# BMS_rev2.net
KiCad netlist of a schematic drawn in Altium Designer
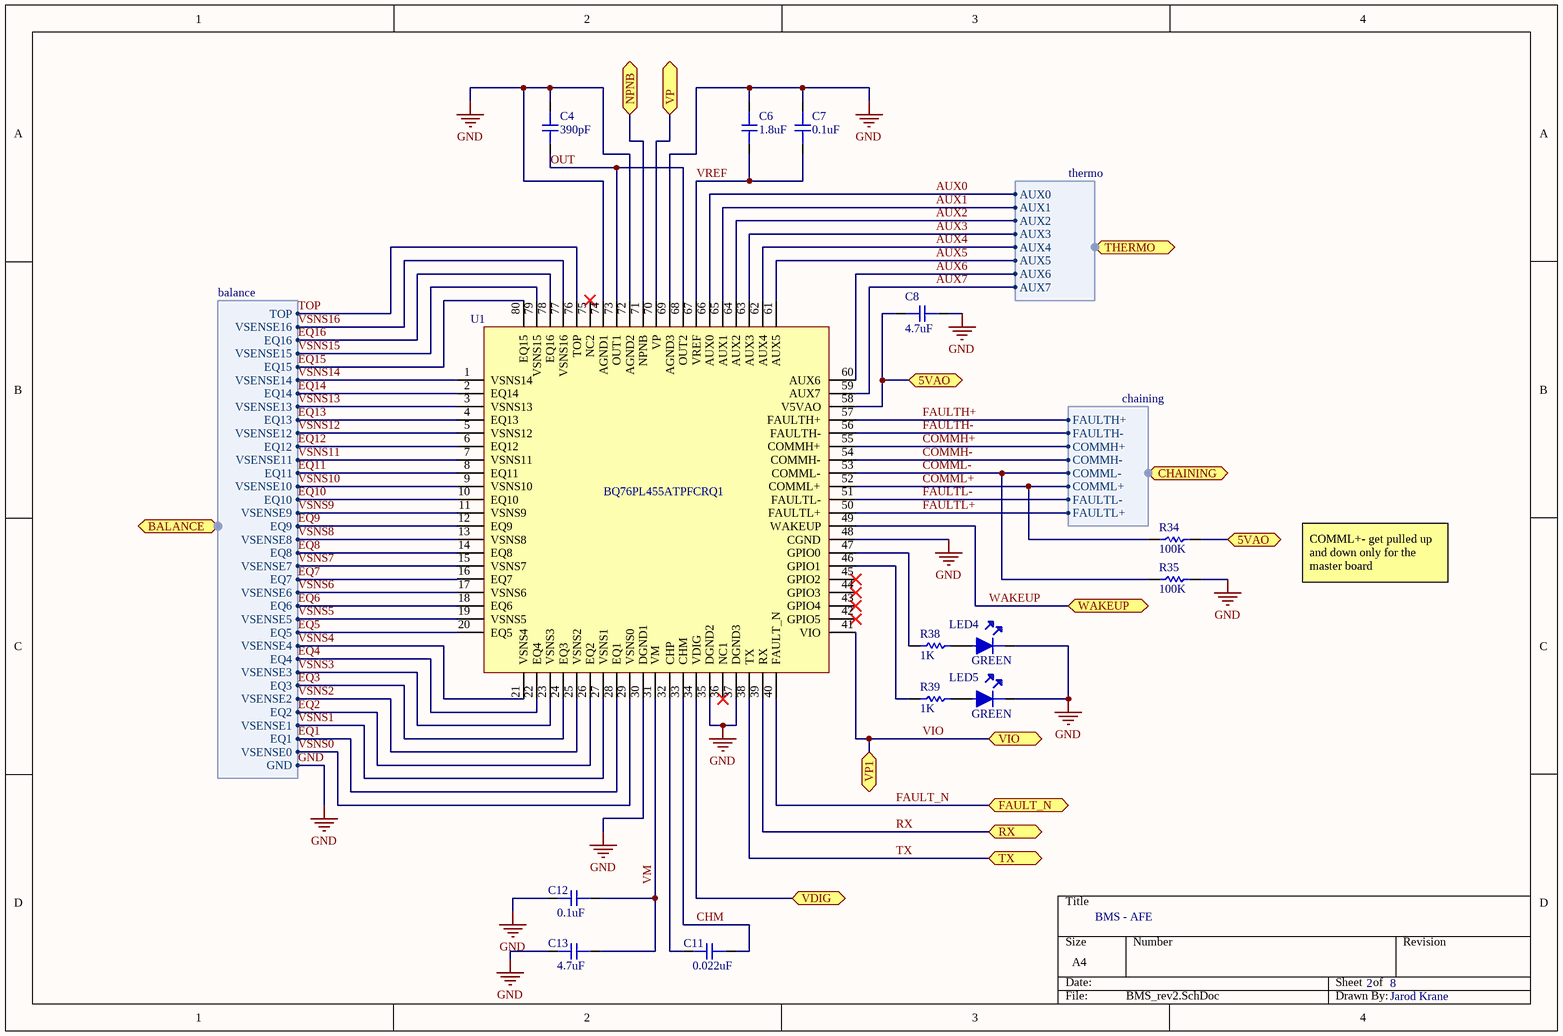
[diagram p0: BMS_rev2.SchDoc]

(export (version "E")
  (design (tool "Eeschema 10.0.6"))
  (components
    (comp (ref "C4")
      (value "390pF")
      (footprint "0805 CAP")
      (description "CAP CER 390PF 50V C0G/NP0 0805")
      (fields
        (field (name "MANUFACTURER") "Kyocera AVX")
        (field (name "MANUFACTURER PART NUMBER") "08055A391JAT2A")
      )
      (libsource (lib "parts") (part "08055A391JAT2A"))
    )
    (comp (ref "C6")
      (value "1.8uF")
      (footprint "1210 cap")
      (description "CAP CER 1.8UF 25V X7R 1210")
      (fields
        (field (name "MANUFACTURER") "KEMET")
        (field (name "MANUFACTURER PART NUMBER") "C1210C185K3RACTU")
      )
      (libsource (lib "parts") (part "C1210C185K3RACTU"))
    )
    (comp (ref "C7")
      (value "0.1uF")
      (footprint "0603 CAP - duplicate")
      (description "CAP CER 0.1UF 50V X7R 0603")
      (fields
        (field (name "MANUFACTURER") "Kyocera AVX")
        (field (name "MANUFACTURER PART NUMBER") "06035C104KAZ2A")
      )
      (libsource (lib "parts") (part "06035C104KAZ2A"))
    )
    (comp (ref "C8")
      (value "4.7uF")
      (footprint "0805 CAP")
      (description "CAP CER 4.7UF 16V X7R 0805")
      (fields
        (field (name "MANUFACTURER") "Samsung")
        (field (name "MANUFACTURER PART NUMBER") "CL21B475KOFNFNE")
      )
      (libsource (lib "parts") (part "CL21B475KOFNFNE"))
    )
    (comp (ref "C11")
      (value "0.022uF")
      (footprint "0603 CAP - duplicate")
      (description "CAP CER 0.022UF 50V X7R 0603")
      (fields
        (field (name "MANUFACTURER") "TDK")
        (field (name "MANUFACTURER PART NUMBER") "C1608X7R1H223K080AA")
      )
      (libsource (lib "parts") (part "C1608X7R1H223K080AA"))
    )
    (comp (ref "C12")
      (value "0.1uF")
      (footprint "0603 CAP - duplicate")
      (description "CAP CER 0.1UF 50V X7R 0603")
      (fields
        (field (name "MANUFACTURER") "Kyocera AVX")
        (field (name "MANUFACTURER PART NUMBER") "06035C104KAZ2A")
      )
      (libsource (lib "parts") (part "06035C104KAZ2A"))
    )
    (comp (ref "C13")
      (value "4.7uF")
      (footprint "0805 CAP")
      (description "CAP CER 4.7UF 16V X7R 0805")
      (fields
        (field (name "MANUFACTURER") "Samsung")
        (field (name "MANUFACTURER PART NUMBER") "CL21B475KOFNFNE")
      )
      (libsource (lib "parts") (part "CL21B475KOFNFNE"))
    )
    (comp (ref "LED4")
      (value "GREEN")
      (footprint "LED2")
      (description "LED GREEN CLEAR 0603 SMD")
      (fields
        (field (name "MANUFACTURER") "Wurth Electronics")
        (field (name "MANUFACTURER PART NUMBER") "150060VS75000")
      )
      (libsource (lib "parts") (part "150060VS75000"))
    )
    (comp (ref "LED5")
      (value "GREEN")
      (footprint "LED2")
      (description "LED GREEN CLEAR 0603 SMD")
      (fields
        (field (name "MANUFACTURER") "Wurth Electronics")
        (field (name "MANUFACTURER PART NUMBER") "150060VS75000")
      )
      (libsource (lib "parts") (part "150060VS75000"))
    )
    (comp (ref "R34")
      (value "100K")
      (footprint "0603 RES")
      (description "RES SMD 100K OHM 1% 1/10W 0603")
      (fields
        (field (name "MANUFACTURER") "Panasonic")
        (field (name "MANUFACTURER PART NUMBER") "ERJ3EKF-1003V")
      )
      (libsource (lib "parts") (part "ERJ-3EKF1003V"))
    )
    (comp (ref "R35")
      (value "100K")
      (footprint "0603 RES")
      (description "RES SMD 100K OHM 1% 1/10W 0603")
      (fields
        (field (name "MANUFACTURER") "Panasonic")
        (field (name "MANUFACTURER PART NUMBER") "ERJ3EKF-1003V")
      )
      (libsource (lib "parts") (part "ERJ-3EKF1003V"))
    )
    (comp (ref "R38")
      (value "1K")
      (footprint "0603 RES")
      (description "RES SMD 1K OHM 1% 1/10W 0603")
      (fields
        (field (name "MANUFACTURER") "Vishay Dale")
        (field (name "MANUFACTURER PART NUMBER") "CRCW06031K00FKEA")
      )
      (libsource (lib "parts") (part "CRCW06031K00FKEA"))
    )
    (comp (ref "R39")
      (value "1K")
      (footprint "0603 RES")
      (description "RES SMD 1K OHM 1% 1/10W 0603")
      (fields
        (field (name "MANUFACTURER") "Vishay Dale")
        (field (name "MANUFACTURER PART NUMBER") "CRCW06031K00FKEA")
      )
      (libsource (lib "parts") (part "CRCW06031K00FKEA"))
    )
    (comp (ref "U1")
      (value "BQ76PL455ATPFCRQ1")
      (footprint "BQ76PL455A-Q1")
      (description "IC BATT MONITOR/PROTECT 80TQFP")
      (fields (field (name "MANUFACTURER") "Texas Instruments"))
      (libsource (lib "parts") (part "BQ76PL455ATPFCRQ1"))
    )
  )
  (nets
    (net (code "4") (name "/5VAO") (class "Default")
      (node (ref "C8") (pin "1") (pinfunction "1_1") (pintype "passive"))
      (node (ref "R34") (pin "2") (pinfunction "2_2") (pintype "passive"))
      (node (ref "U1") (pin "58") (pinfunction "V5VAO_58") (pintype "passive"))
    )
    (net (code "5") (name "/AUX0") (class "Default")
      (node (ref "U1") (pin "66") (pinfunction "AUX0_66") (pintype "passive"))
    )
    (net (code "6") (name "/AUX1") (class "Default")
      (node (ref "U1") (pin "65") (pinfunction "AUX1_65") (pintype "passive"))
    )
    (net (code "7") (name "/AUX2") (class "Default")
      (node (ref "U1") (pin "64") (pinfunction "AUX2_64") (pintype "passive"))
    )
    (net (code "8") (name "/AUX3") (class "Default")
      (node (ref "U1") (pin "63") (pinfunction "AUX3_63") (pintype "passive"))
    )
    (net (code "9") (name "/AUX4") (class "Default")
      (node (ref "U1") (pin "62") (pinfunction "AUX4_62") (pintype "passive"))
    )
    (net (code "10") (name "/AUX5") (class "Default")
      (node (ref "U1") (pin "61") (pinfunction "AUX5_61") (pintype "passive"))
    )
    (net (code "11") (name "/AUX6") (class "Default")
      (node (ref "U1") (pin "60") (pinfunction "AUX6_60") (pintype "passive"))
    )
    (net (code "12") (name "/AUX7") (class "Default")
      (node (ref "U1") (pin "59") (pinfunction "AUX7_59") (pintype "passive"))
    )
    (net (code "13") (name "/CHM") (class "Default")
      (node (ref "C11") (pin "2") (pinfunction "2_2") (pintype "passive"))
      (node (ref "U1") (pin "33") (pinfunction "CHM_33") (pintype "passive"))
    )
    (net (code "14") (name "/COMMH+") (class "Default")
      (node (ref "U1") (pin "55") (pinfunction "COMMH+_55") (pintype "passive"))
    )
    (net (code "15") (name "/COMMH-") (class "Default")
      (node (ref "U1") (pin "54") (pinfunction "COMMH-_54") (pintype "passive"))
    )
    (net (code "16") (name "/COMML+") (class "Default")
      (node (ref "R34") (pin "1") (pinfunction "1_1") (pintype "passive"))
      (node (ref "U1") (pin "52") (pinfunction "COMML+_52") (pintype "passive"))
    )
    (net (code "17") (name "/COMML-") (class "Default")
      (node (ref "R35") (pin "1") (pinfunction "1_1") (pintype "passive"))
      (node (ref "U1") (pin "53") (pinfunction "COMML-_53") (pintype "passive"))
    )
    (net (code "18") (name "/EQ1") (class "Default")
      (node (ref "U1") (pin "28") (pinfunction "EQ1_28") (pintype "passive"))
    )
    (net (code "19") (name "/EQ2") (class "Default")
      (node (ref "U1") (pin "26") (pinfunction "EQ2_26") (pintype "passive"))
    )
    (net (code "20") (name "/EQ3") (class "Default")
      (node (ref "U1") (pin "24") (pinfunction "EQ3_24") (pintype "passive"))
    )
    (net (code "21") (name "/EQ4") (class "Default")
      (node (ref "U1") (pin "22") (pinfunction "EQ4_22") (pintype "passive"))
    )
    (net (code "22") (name "/EQ5") (class "Default")
      (node (ref "U1") (pin "20") (pinfunction "EQ5_20") (pintype "passive"))
    )
    (net (code "23") (name "/EQ6") (class "Default")
      (node (ref "U1") (pin "18") (pinfunction "EQ6_18") (pintype "passive"))
    )
    (net (code "24") (name "/EQ7") (class "Default")
      (node (ref "U1") (pin "16") (pinfunction "EQ7_16") (pintype "passive"))
    )
    (net (code "25") (name "/EQ8") (class "Default")
      (node (ref "U1") (pin "14") (pinfunction "EQ8_14") (pintype "passive"))
    )
    (net (code "26") (name "/EQ9") (class "Default")
      (node (ref "U1") (pin "12") (pinfunction "EQ9_12") (pintype "passive"))
    )
    (net (code "27") (name "/EQ10") (class "Default")
      (node (ref "U1") (pin "10") (pinfunction "EQ10_10") (pintype "passive"))
    )
    (net (code "28") (name "/EQ11") (class "Default")
      (node (ref "U1") (pin "8") (pinfunction "EQ11_8") (pintype "passive"))
    )
    (net (code "29") (name "/EQ12") (class "Default")
      (node (ref "U1") (pin "6") (pinfunction "EQ12_6") (pintype "passive"))
    )
    (net (code "30") (name "/EQ13") (class "Default")
      (node (ref "U1") (pin "4") (pinfunction "EQ13_4") (pintype "passive"))
    )
    (net (code "31") (name "/EQ14") (class "Default")
      (node (ref "U1") (pin "2") (pinfunction "EQ14_2") (pintype "passive"))
    )
    (net (code "32") (name "/EQ15") (class "Default")
      (node (ref "U1") (pin "80") (pinfunction "EQ15_80") (pintype "passive"))
    )
    (net (code "33") (name "/EQ16") (class "Default")
      (node (ref "U1") (pin "78") (pinfunction "EQ16_78") (pintype "passive"))
    )
    (net (code "34") (name "/FAULTH+") (class "Default")
      (node (ref "U1") (pin "57") (pinfunction "FAULTH+_57") (pintype "passive"))
    )
    (net (code "35") (name "/FAULTH-") (class "Default")
      (node (ref "U1") (pin "56") (pinfunction "FAULTH-_56") (pintype "passive"))
    )
    (net (code "36") (name "/FAULTL+") (class "Default")
      (node (ref "U1") (pin "50") (pinfunction "FAULTL+_50") (pintype "passive"))
    )
    (net (code "37") (name "/FAULTL-") (class "Default")
      (node (ref "U1") (pin "51") (pinfunction "FAULTL-_51") (pintype "passive"))
    )
    (net (code "38") (name "/FAULT_N") (class "Default")
      (node (ref "U1") (pin "40") (pinfunction "FAULT_N_40") (pintype "passive"))
    )
    (net (code "39") (name "/NPNB") (class "Default")
      (node (ref "U1") (pin "71") (pinfunction "NPNB_71") (pintype "passive"))
    )
    (net (code "40") (name "/OUT") (class "Default")
      (node (ref "C4") (pin "1") (pinfunction "1_1") (pintype "passive"))
      (node (ref "U1") (pin "68") (pinfunction "OUT2_68") (pintype "passive"))
      (node (ref "U1") (pin "73") (pinfunction "OUT1_73") (pintype "passive"))
    )
    (net (code "41") (name "/RX") (class "Default")
      (node (ref "U1") (pin "39") (pinfunction "RX_39") (pintype "passive"))
    )
    (net (code "42") (name "/TOP") (class "Default")
      (node (ref "U1") (pin "76") (pinfunction "TOP_76") (pintype "passive"))
    )
    (net (code "43") (name "/TX") (class "Default")
      (node (ref "U1") (pin "38") (pinfunction "TX_38") (pintype "passive"))
    )
    (net (code "44") (name "/VDIG") (class "Default")
      (node (ref "U1") (pin "34") (pinfunction "VDIG_34") (pintype "passive"))
    )
    (net (code "45") (name "/VIO") (class "Default")
      (node (ref "U1") (pin "41") (pinfunction "VIO_41") (pintype "passive"))
    )
    (net (code "46") (name "/VM") (class "Default")
      (node (ref "C12") (pin "2") (pinfunction "2_2") (pintype "passive"))
      (node (ref "C13") (pin "2") (pinfunction "2_2") (pintype "passive"))
      (node (ref "U1") (pin "31") (pinfunction "VM_31") (pintype "passive"))
    )
    (net (code "47") (name "/VP") (class "Default")
      (node (ref "U1") (pin "70") (pinfunction "VP_70") (pintype "passive"))
    )
    (net (code "48") (name "/VREF") (class "Default")
      (node (ref "C6") (pin "1") (pinfunction "1_1") (pintype "passive"))
      (node (ref "C7") (pin "1") (pinfunction "1_1") (pintype "passive"))
      (node (ref "U1") (pin "67") (pinfunction "VREF_67") (pintype "passive"))
    )
    (net (code "49") (name "/VSNS0") (class "Default")
      (node (ref "U1") (pin "29") (pinfunction "VSNS0_29") (pintype "passive"))
    )
    (net (code "50") (name "/VSNS1") (class "Default")
      (node (ref "U1") (pin "27") (pinfunction "VSNS1_27") (pintype "passive"))
    )
    (net (code "51") (name "/VSNS2") (class "Default")
      (node (ref "U1") (pin "25") (pinfunction "VSNS2_25") (pintype "passive"))
    )
    (net (code "52") (name "/VSNS3") (class "Default")
      (node (ref "U1") (pin "23") (pinfunction "VSNS3_23") (pintype "passive"))
    )
    (net (code "53") (name "/VSNS4") (class "Default")
      (node (ref "U1") (pin "21") (pinfunction "VSNS4_21") (pintype "passive"))
    )
    (net (code "54") (name "/VSNS5") (class "Default")
      (node (ref "U1") (pin "19") (pinfunction "VSNS5_19") (pintype "passive"))
    )
    (net (code "55") (name "/VSNS6") (class "Default")
      (node (ref "U1") (pin "17") (pinfunction "VSNS6_17") (pintype "passive"))
    )
    (net (code "56") (name "/VSNS7") (class "Default")
      (node (ref "U1") (pin "15") (pinfunction "VSNS7_15") (pintype "passive"))
    )
    (net (code "57") (name "/VSNS8") (class "Default")
      (node (ref "U1") (pin "13") (pinfunction "VSNS8_13") (pintype "passive"))
    )
    (net (code "58") (name "/VSNS9") (class "Default")
      (node (ref "U1") (pin "11") (pinfunction "VSNS9_11") (pintype "passive"))
    )
    (net (code "59") (name "/VSNS10") (class "Default")
      (node (ref "U1") (pin "9") (pinfunction "VSNS10_9") (pintype "passive"))
    )
    (net (code "60") (name "/VSNS11") (class "Default")
      (node (ref "U1") (pin "7") (pinfunction "VSNS11_7") (pintype "passive"))
    )
    (net (code "61") (name "/VSNS12") (class "Default")
      (node (ref "U1") (pin "5") (pinfunction "VSNS12_5") (pintype "passive"))
    )
    (net (code "62") (name "/VSNS13") (class "Default")
      (node (ref "U1") (pin "3") (pinfunction "VSNS13_3") (pintype "passive"))
    )
    (net (code "63") (name "/VSNS14") (class "Default")
      (node (ref "U1") (pin "1") (pinfunction "VSNS14_1") (pintype "passive"))
    )
    (net (code "64") (name "/VSNS15") (class "Default")
      (node (ref "U1") (pin "79") (pinfunction "VSNS15_79") (pintype "passive"))
    )
    (net (code "65") (name "/VSNS16") (class "Default")
      (node (ref "U1") (pin "77") (pinfunction "VSNS16_77") (pintype "passive"))
    )
    (net (code "66") (name "/WAKEUP") (class "Default")
      (node (ref "U1") (pin "49") (pinfunction "WAKEUP_49") (pintype "passive"))
    )
    (net (code "70") (name "GND") (class "Default")
      (node (ref "C12") (pin "1") (pinfunction "1_1") (pintype "passive"))
      (node (ref "C13") (pin "1") (pinfunction "1_1") (pintype "passive"))
      (node (ref "C4") (pin "2") (pinfunction "2_2") (pintype "passive"))
      (node (ref "C6") (pin "2") (pinfunction "2_2") (pintype "passive"))
      (node (ref "C7") (pin "2") (pinfunction "2_2") (pintype "passive"))
      (node (ref "C8") (pin "2") (pinfunction "2_2") (pintype "passive"))
      (node (ref "LED4") (pin "2") (pinfunction "2_2") (pintype "passive"))
      (node (ref "LED5") (pin "2") (pinfunction "2_2") (pintype "passive"))
      (node (ref "R35") (pin "2") (pinfunction "2_2") (pintype "passive"))
      (node (ref "U1") (pin "30") (pinfunction "DGND1_30") (pintype "passive"))
      (node (ref "U1") (pin "35") (pinfunction "DGND2_35") (pintype "passive"))
      (node (ref "U1") (pin "37") (pinfunction "DGND3_37") (pintype "passive"))
      (node (ref "U1") (pin "48") (pinfunction "CGND_48") (pintype "passive"))
      (node (ref "U1") (pin "69") (pinfunction "AGND3_69") (pintype "passive"))
      (node (ref "U1") (pin "72") (pinfunction "AGND2_72") (pintype "passive"))
      (node (ref "U1") (pin "74") (pinfunction "AGND1_74") (pintype "passive"))
    )
    (net (code "71") (name "Net-(LED4-Pad1)") (class "Default")
      (node (ref "LED4") (pin "1") (pinfunction "1_1") (pintype "passive"))
      (node (ref "R38") (pin "2") (pinfunction "2_2") (pintype "passive"))
    )
    (net (code "72") (name "Net-(LED5-Pad1)") (class "Default")
      (node (ref "LED5") (pin "1") (pinfunction "1_1") (pintype "passive"))
      (node (ref "R39") (pin "2") (pinfunction "2_2") (pintype "passive"))
    )
    (net (code "73") (name "Net-(U1-CHP)") (class "Default")
      (node (ref "C11") (pin "1") (pinfunction "1_1") (pintype "passive"))
      (node (ref "U1") (pin "32") (pinfunction "CHP_32") (pintype "passive"))
    )
    (net (code "74") (name "Net-(U1-GPIO0)") (class "Default")
      (node (ref "R38") (pin "1") (pinfunction "1_1") (pintype "passive"))
      (node (ref "U1") (pin "47") (pinfunction "GPIO0_47") (pintype "passive"))
    )
    (net (code "75") (name "Net-(U1-GPIO1)") (class "Default")
      (node (ref "R39") (pin "1") (pinfunction "1_1") (pintype "passive"))
      (node (ref "U1") (pin "46") (pinfunction "GPIO1_46") (pintype "passive"))
    )
    (net (code "76") (name "unconnected-(U1-GPIO2-Pad45)") (class "Default")
      (node (ref "U1") (pin "45") (pinfunction "GPIO2_45") (pintype "passive+no_connect"))
    )
    (net (code "77") (name "unconnected-(U1-GPIO3-Pad44)") (class "Default")
      (node (ref "U1") (pin "44") (pinfunction "GPIO3_44") (pintype "passive+no_connect"))
    )
    (net (code "78") (name "unconnected-(U1-GPIO4-Pad43)") (class "Default")
      (node (ref "U1") (pin "43") (pinfunction "GPIO4_43") (pintype "passive+no_connect"))
    )
    (net (code "79") (name "unconnected-(U1-GPIO5-Pad42)") (class "Default")
      (node (ref "U1") (pin "42") (pinfunction "GPIO5_42") (pintype "passive+no_connect"))
    )
    (net (code "80") (name "unconnected-(U1-NC1-Pad36)") (class "Default")
      (node (ref "U1") (pin "36") (pinfunction "NC1_36") (pintype "passive+no_connect"))
    )
    (net (code "81") (name "unconnected-(U1-NC2-Pad75)") (class "Default")
      (node (ref "U1") (pin "75") (pinfunction "NC2_75") (pintype "passive+no_connect"))
    )
  )
)
